# OneLedBlinker.net
KiCad netlist of a schematic drawn in EAGLE
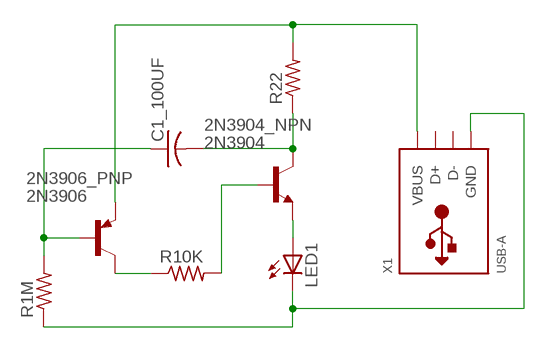
[diagram p0: schematic, sheet 1]

(export (version "E")
  (design (tool "Eeschema 10.0.6"))
  (components
    (comp (ref "2N3904_NPN")
      (value "2N3904")
      (footprint "eagle-import:TO92")
      (libsource (lib "eagle-import") (part "2N3904"))
    )
    (comp (ref "2N3906_PNP")
      (value "2N3906")
      (footprint "eagle-import:TO92")
      (libsource (lib "eagle-import") (part "2N3906"))
    )
    (comp (ref "C1_100UF")
      (value "C-US025-030X050")
      (footprint "eagle-import:C025-030X050")
      (libsource (lib "eagle-import") (part "C-US025-030X050"))
    )
    (comp (ref "LED1")
      (value "LED5MM")
      (footprint "eagle-import:LED5MM")
      (libsource (lib "eagle-import") (part "LED5MM"))
    )
    (comp (ref "R1M")
      (value "R-US_0207/10")
      (footprint "eagle-import:0207_10")
      (libsource (lib "eagle-import") (part "R-US_0207/10"))
    )
    (comp (ref "R10K")
      (value "R-US_0207/10")
      (footprint "eagle-import:0207_10")
      (libsource (lib "eagle-import") (part "R-US_0207/10"))
    )
    (comp (ref "R22")
      (value "R-US_0207/10")
      (footprint "eagle-import:0207_10")
      (libsource (lib "eagle-import") (part "R-US_0207/10"))
    )
    (comp (ref "X1")
      (value "USB-A")
      (footprint "eagle-import:MOLEX_480371000")
      (libsource (lib "eagle-import") (part "USB-A"))
    )
  )
  (nets
    (net (code "1") (name "Net-(2N3904_NPN-B)") (class "Default")
      (node (ref "2N3904_NPN") (pin "2") (pinfunction "B_2") (pintype "passive"))
      (node (ref "R10K") (pin "2") (pinfunction "2_2") (pintype "passive"))
    )
    (net (code "2") (name "Net-(2N3904_NPN-C)") (class "Default")
      (node (ref "2N3904_NPN") (pin "1") (pinfunction "C_1") (pintype "passive"))
      (node (ref "C1_100UF") (pin "2") (pinfunction "2_2") (pintype "passive"))
      (node (ref "R22") (pin "1") (pinfunction "1_1") (pintype "passive"))
    )
    (net (code "3") (name "Net-(2N3904_NPN-E)") (class "Default")
      (node (ref "2N3904_NPN") (pin "3") (pinfunction "E_3") (pintype "passive"))
      (node (ref "LED1") (pin "A") (pinfunction "A_A") (pintype "passive"))
    )
    (net (code "4") (name "Net-(2N3906_PNP-B)") (class "Default")
      (node (ref "2N3906_PNP") (pin "2") (pinfunction "B_2") (pintype "passive"))
      (node (ref "C1_100UF") (pin "1") (pinfunction "1_1") (pintype "passive"))
      (node (ref "R1M") (pin "2") (pinfunction "2_2") (pintype "passive"))
    )
    (net (code "5") (name "Net-(2N3906_PNP-C)") (class "Default")
      (node (ref "2N3906_PNP") (pin "1") (pinfunction "C_1") (pintype "passive"))
      (node (ref "R10K") (pin "1") (pinfunction "1_1") (pintype "passive"))
    )
    (net (code "6") (name "Net-(2N3906_PNP-E)") (class "Default")
      (node (ref "2N3906_PNP") (pin "3") (pinfunction "E_3") (pintype "passive"))
      (node (ref "R22") (pin "2") (pinfunction "2_2") (pintype "passive"))
      (node (ref "X1") (pin "1") (pinfunction "VBUS_1") (pintype "power_in"))
    )
    (net (code "7") (name "Net-(LED1-C)") (class "Default")
      (node (ref "LED1") (pin "K") (pinfunction "C_K") (pintype "passive"))
      (node (ref "R1M") (pin "1") (pinfunction "1_1") (pintype "passive"))
      (node (ref "X1") (pin "4") (pinfunction "GND_4") (pintype "power_in"))
    )
    (net (code "8") (name "unconnected-(X1-D+-Pad3)") (class "Default")
      (node (ref "X1") (pin "3") (pinfunction "D+_3") (pintype "bidirectional"))
    )
    (net (code "9") (name "unconnected-(X1-D--Pad2)") (class "Default")
      (node (ref "X1") (pin "2") (pinfunction "D-_2") (pintype "bidirectional"))
    )
  )
)
